# SNES_RGB_SV.net
KiCad netlist of a schematic drawn in EAGLE
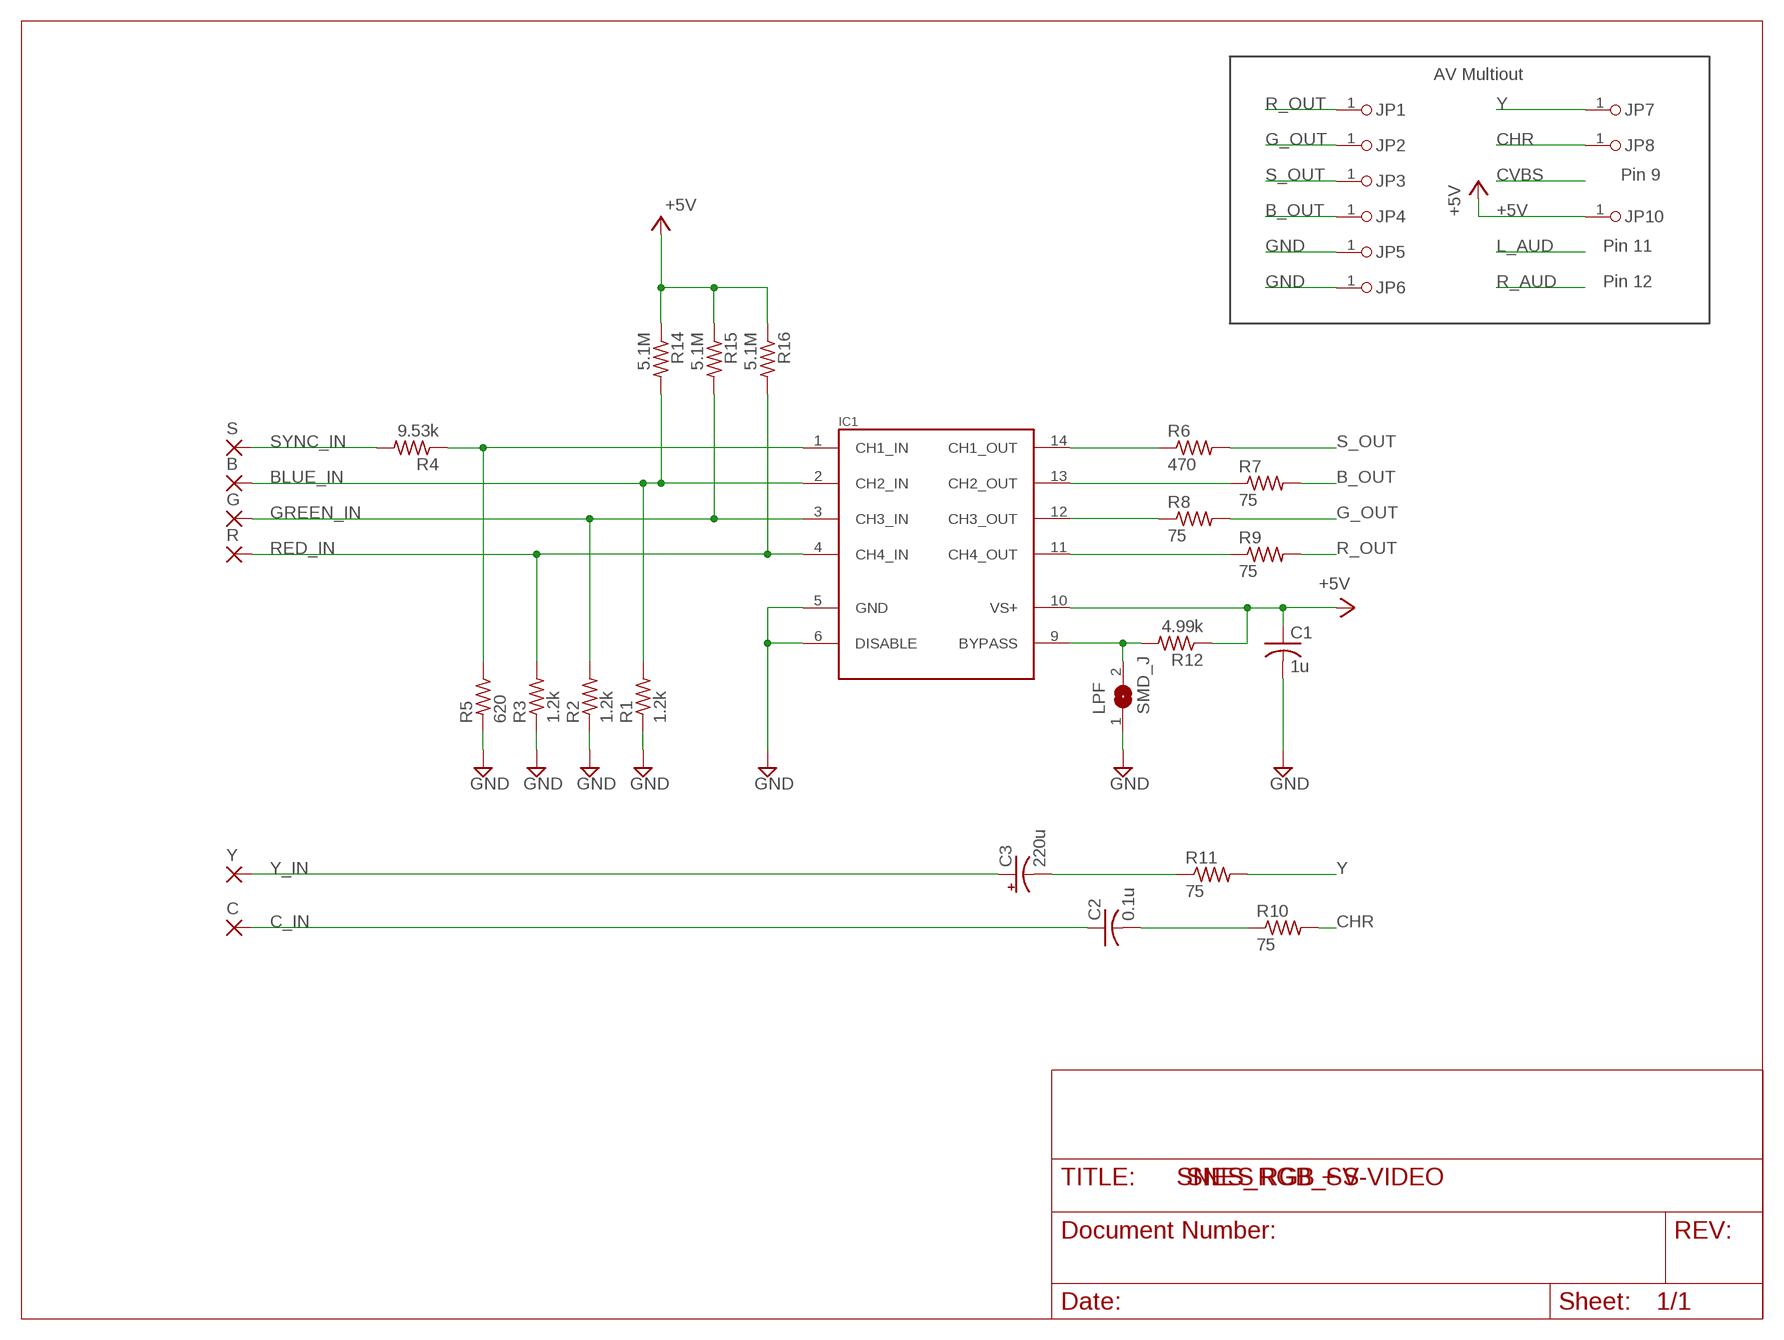
[diagram p0: schematic, sheet 1]

(export (version "E")
  (design (tool "Eeschema 10.0.6"))
  (components
    (comp (ref "B")
      (value "SMD2")
      (footprint "eagle-import:SMD1,27-2,54")
      (libsource (lib "eagle-import") (part "SMD2"))
    )
    (comp (ref "C")
      (value "SMD2")
      (footprint "eagle-import:SMD1,27-2,54")
      (libsource (lib "eagle-import") (part "SMD2"))
    )
    (comp (ref "C1")
      (value "1u")
      (footprint "eagle-import:C0603")
      (libsource (lib "eagle-import") (part "C-USC0603"))
    )
    (comp (ref "C2")
      (value "0.1u")
      (footprint "eagle-import:C0603")
      (libsource (lib "eagle-import") (part "C-USC0603"))
    )
    (comp (ref "C3")
      (value "220u")
      (footprint "eagle-import:C_6032-28R")
      (libsource (lib "eagle-import") (part "CPOL-USC/6032-28R"))
    )
    (comp (ref "G")
      (value "SMD2")
      (footprint "eagle-import:SMD1,27-2,54")
      (libsource (lib "eagle-import") (part "SMD2"))
    )
    (comp (ref "IC1")
      (value "THS7374IPWR")
      (footprint "eagle-import:TSSOP14")
      (libsource (lib "eagle-import") (part "THS7374IPWR"))
    )
    (comp (ref "JP1")
      (value "PINHD-1X1")
      (footprint "eagle-import:1X01")
      (libsource (lib "eagle-import") (part "PINHD-1X1"))
    )
    (comp (ref "JP2")
      (value "PINHD-1X1")
      (footprint "eagle-import:1X01")
      (libsource (lib "eagle-import") (part "PINHD-1X1"))
    )
    (comp (ref "JP3")
      (value "PINHD-1X1")
      (footprint "eagle-import:1X01")
      (libsource (lib "eagle-import") (part "PINHD-1X1"))
    )
    (comp (ref "JP4")
      (value "PINHD-1X1")
      (footprint "eagle-import:1X01")
      (libsource (lib "eagle-import") (part "PINHD-1X1"))
    )
    (comp (ref "JP5")
      (value "PINHD-1X1")
      (footprint "eagle-import:1X01")
      (libsource (lib "eagle-import") (part "PINHD-1X1"))
    )
    (comp (ref "JP6")
      (value "PINHD-1X1")
      (footprint "eagle-import:1X01")
      (libsource (lib "eagle-import") (part "PINHD-1X1"))
    )
    (comp (ref "JP7")
      (value "PINHD-1X1")
      (footprint "eagle-import:1X01")
      (libsource (lib "eagle-import") (part "PINHD-1X1"))
    )
    (comp (ref "JP8")
      (value "PINHD-1X1")
      (footprint "eagle-import:1X01")
      (libsource (lib "eagle-import") (part "PINHD-1X1"))
    )
    (comp (ref "JP10")
      (value "PINHD-1X1")
      (footprint "eagle-import:1X01")
      (libsource (lib "eagle-import") (part "PINHD-1X1"))
    )
    (comp (ref "LPF")
      (value "SMD_J")
      (footprint "eagle-import:SJ")
      (libsource (lib "eagle-import") (part "SMD_J"))
    )
    (comp (ref "R")
      (value "SMD2")
      (footprint "eagle-import:SMD1,27-2,54")
      (libsource (lib "eagle-import") (part "SMD2"))
    )
    (comp (ref "R1")
      (value "1.2k")
      (footprint "eagle-import:R0603")
      (libsource (lib "eagle-import") (part "R-US_R0603"))
    )
    (comp (ref "R2")
      (value "1.2k")
      (footprint "eagle-import:R0603")
      (libsource (lib "eagle-import") (part "R-US_R0603"))
    )
    (comp (ref "R3")
      (value "1.2k")
      (footprint "eagle-import:R0603")
      (libsource (lib "eagle-import") (part "R-US_R0603"))
    )
    (comp (ref "R4")
      (value "9.53k")
      (footprint "eagle-import:R0603")
      (libsource (lib "eagle-import") (part "R-US_R0603"))
    )
    (comp (ref "R5")
      (value "620")
      (footprint "eagle-import:R0603")
      (libsource (lib "eagle-import") (part "R-US_R0603"))
    )
    (comp (ref "R6")
      (value "470")
      (footprint "eagle-import:R0603")
      (libsource (lib "eagle-import") (part "R-US_R0603"))
    )
    (comp (ref "R7")
      (value "75")
      (footprint "eagle-import:R0603")
      (libsource (lib "eagle-import") (part "R-US_R0603"))
    )
    (comp (ref "R8")
      (value "75")
      (footprint "eagle-import:R0603")
      (libsource (lib "eagle-import") (part "R-US_R0603"))
    )
    (comp (ref "R9")
      (value "75")
      (footprint "eagle-import:R0603")
      (libsource (lib "eagle-import") (part "R-US_R0603"))
    )
    (comp (ref "R10")
      (value "75")
      (footprint "eagle-import:R0603")
      (libsource (lib "eagle-import") (part "R-US_R0603"))
    )
    (comp (ref "R11")
      (value "75")
      (footprint "eagle-import:R0603")
      (libsource (lib "eagle-import") (part "R-US_R0603"))
    )
    (comp (ref "R12")
      (value "4.99k")
      (footprint "eagle-import:R0603")
      (libsource (lib "eagle-import") (part "R-US_R0603"))
    )
    (comp (ref "R14")
      (value "5.1M")
      (footprint "eagle-import:R0603")
      (libsource (lib "eagle-import") (part "R-US_R0603"))
    )
    (comp (ref "R15")
      (value "5.1M")
      (footprint "eagle-import:R0603")
      (libsource (lib "eagle-import") (part "R-US_R0603"))
    )
    (comp (ref "R16")
      (value "5.1M")
      (footprint "eagle-import:R0603")
      (libsource (lib "eagle-import") (part "R-US_R0603"))
    )
    (comp (ref "S")
      (value "SMD2")
      (footprint "eagle-import:SMD1,27-2,54")
      (libsource (lib "eagle-import") (part "SMD2"))
    )
    (comp (ref "Y")
      (value "SMD2")
      (footprint "eagle-import:SMD1,27-2,54")
      (libsource (lib "eagle-import") (part "SMD2"))
    )
  )
  (nets
    (net (code "1") (name "+5V") (class "Default")
      (node (ref "C1") (pin "1") (pinfunction "1_1") (pintype "passive"))
      (node (ref "IC1") (pin "10") (pinfunction "VS+_10") (pintype "bidirectional"))
      (node (ref "JP10") (pin "1") (pinfunction "1_1") (pintype "passive"))
      (node (ref "R12") (pin "1") (pinfunction "1_1") (pintype "passive"))
      (node (ref "R14") (pin "1") (pinfunction "1_1") (pintype "passive"))
      (node (ref "R15") (pin "1") (pinfunction "1_1") (pintype "passive"))
      (node (ref "R16") (pin "1") (pinfunction "1_1") (pintype "passive"))
    )
    (net (code "2") (name "/BLUE_IN") (class "Default")
      (node (ref "B") (pin "1") (pinfunction "P_1") (pintype "passive"))
      (node (ref "IC1") (pin "2") (pinfunction "CH2_IN_2") (pintype "bidirectional"))
      (node (ref "R1") (pin "2") (pinfunction "2_2") (pintype "passive"))
      (node (ref "R14") (pin "2") (pinfunction "2_2") (pintype "passive"))
    )
    (net (code "3") (name "/B_OUT") (class "Default")
      (node (ref "JP4") (pin "1") (pinfunction "1_1") (pintype "passive"))
      (node (ref "R7") (pin "2") (pinfunction "2_2") (pintype "passive"))
    )
    (net (code "4") (name "/CHR") (class "Default")
      (node (ref "JP8") (pin "1") (pinfunction "1_1") (pintype "passive"))
      (node (ref "R10") (pin "2") (pinfunction "2_2") (pintype "passive"))
    )
    (net (code "6") (name "/C_IN") (class "Default")
      (node (ref "C") (pin "1") (pinfunction "P_1") (pintype "passive"))
      (node (ref "C2") (pin "1") (pinfunction "1_1") (pintype "passive"))
    )
    (net (code "7") (name "/GREEN_IN") (class "Default")
      (node (ref "G") (pin "1") (pinfunction "P_1") (pintype "passive"))
      (node (ref "IC1") (pin "3") (pinfunction "CH3_IN_3") (pintype "bidirectional"))
      (node (ref "R15") (pin "2") (pinfunction "2_2") (pintype "passive"))
      (node (ref "R2") (pin "2") (pinfunction "2_2") (pintype "passive"))
    )
    (net (code "8") (name "/G_OUT") (class "Default")
      (node (ref "JP2") (pin "1") (pinfunction "1_1") (pintype "passive"))
      (node (ref "R8") (pin "2") (pinfunction "2_2") (pintype "passive"))
    )
    (net (code "10") (name "/RED_IN") (class "Default")
      (node (ref "IC1") (pin "4") (pinfunction "CH4_IN_4") (pintype "bidirectional"))
      (node (ref "R") (pin "1") (pinfunction "P_1") (pintype "passive"))
      (node (ref "R16") (pin "2") (pinfunction "2_2") (pintype "passive"))
      (node (ref "R3") (pin "2") (pinfunction "2_2") (pintype "passive"))
    )
    (net (code "12") (name "/R_OUT") (class "Default")
      (node (ref "JP1") (pin "1") (pinfunction "1_1") (pintype "passive"))
      (node (ref "R9") (pin "2") (pinfunction "2_2") (pintype "passive"))
    )
    (net (code "13") (name "/SYNC_IN") (class "Default")
      (node (ref "R4") (pin "2") (pinfunction "2_2") (pintype "passive"))
      (node (ref "S") (pin "1") (pinfunction "P_1") (pintype "passive"))
    )
    (net (code "14") (name "/S_OUT") (class "Default")
      (node (ref "JP3") (pin "1") (pinfunction "1_1") (pintype "passive"))
      (node (ref "R6") (pin "2") (pinfunction "2_2") (pintype "passive"))
    )
    (net (code "15") (name "/Y") (class "Default")
      (node (ref "JP7") (pin "1") (pinfunction "1_1") (pintype "passive"))
      (node (ref "R11") (pin "2") (pinfunction "2_2") (pintype "passive"))
    )
    (net (code "16") (name "/Y_IN") (class "Default")
      (node (ref "C3") (pin "+") (pinfunction "+_+") (pintype "passive"))
      (node (ref "Y") (pin "1") (pinfunction "P_1") (pintype "passive"))
    )
    (net (code "17") (name "GND") (class "Default")
      (node (ref "C1") (pin "2") (pinfunction "2_2") (pintype "passive"))
      (node (ref "IC1") (pin "5") (pinfunction "GND_5") (pintype "bidirectional"))
      (node (ref "IC1") (pin "6") (pinfunction "DISABLE_6") (pintype "bidirectional"))
      (node (ref "JP5") (pin "1") (pinfunction "1_1") (pintype "passive"))
      (node (ref "JP6") (pin "1") (pinfunction "1_1") (pintype "passive"))
      (node (ref "LPF") (pin "1") (pinfunction "1_1") (pintype "passive"))
      (node (ref "R1") (pin "1") (pinfunction "1_1") (pintype "passive"))
      (node (ref "R2") (pin "1") (pinfunction "1_1") (pintype "passive"))
      (node (ref "R3") (pin "1") (pinfunction "1_1") (pintype "passive"))
      (node (ref "R5") (pin "2") (pinfunction "2_2") (pintype "passive"))
    )
    (net (code "18") (name "Net-(C2-Pad2)") (class "Default")
      (node (ref "C2") (pin "2") (pinfunction "2_2") (pintype "passive"))
      (node (ref "R10") (pin "1") (pinfunction "1_1") (pintype "passive"))
    )
    (net (code "19") (name "Net-(C3-Pad-)") (class "Default")
      (node (ref "C3") (pin "-") (pinfunction "-_-") (pintype "passive"))
      (node (ref "R11") (pin "1") (pinfunction "1_1") (pintype "passive"))
    )
    (net (code "20") (name "Net-(IC1-BYPASS)") (class "Default")
      (node (ref "IC1") (pin "9") (pinfunction "BYPASS_9") (pintype "bidirectional"))
      (node (ref "LPF") (pin "2") (pinfunction "2_2") (pintype "passive"))
      (node (ref "R12") (pin "2") (pinfunction "2_2") (pintype "passive"))
    )
    (net (code "21") (name "Net-(IC1-CH1_IN)") (class "Default")
      (node (ref "IC1") (pin "1") (pinfunction "CH1_IN_1") (pintype "bidirectional"))
      (node (ref "R4") (pin "1") (pinfunction "1_1") (pintype "passive"))
      (node (ref "R5") (pin "1") (pinfunction "1_1") (pintype "passive"))
    )
    (net (code "22") (name "Net-(IC1-CH1_OUT)") (class "Default")
      (node (ref "IC1") (pin "14") (pinfunction "CH1_OUT_14") (pintype "bidirectional"))
      (node (ref "R6") (pin "1") (pinfunction "1_1") (pintype "passive"))
    )
    (net (code "23") (name "Net-(IC1-CH2_OUT)") (class "Default")
      (node (ref "IC1") (pin "13") (pinfunction "CH2_OUT_13") (pintype "bidirectional"))
      (node (ref "R7") (pin "1") (pinfunction "1_1") (pintype "passive"))
    )
    (net (code "24") (name "Net-(IC1-CH3_OUT)") (class "Default")
      (node (ref "IC1") (pin "12") (pinfunction "CH3_OUT_12") (pintype "bidirectional"))
      (node (ref "R8") (pin "1") (pinfunction "1_1") (pintype "passive"))
    )
    (net (code "25") (name "Net-(IC1-CH4_OUT)") (class "Default")
      (node (ref "IC1") (pin "11") (pinfunction "CH4_OUT_11") (pintype "bidirectional"))
      (node (ref "R9") (pin "1") (pinfunction "1_1") (pintype "passive"))
    )
  )
)
